# DC_Power_Regulation.net
KiCad netlist of a schematic drawn in Altium Designer
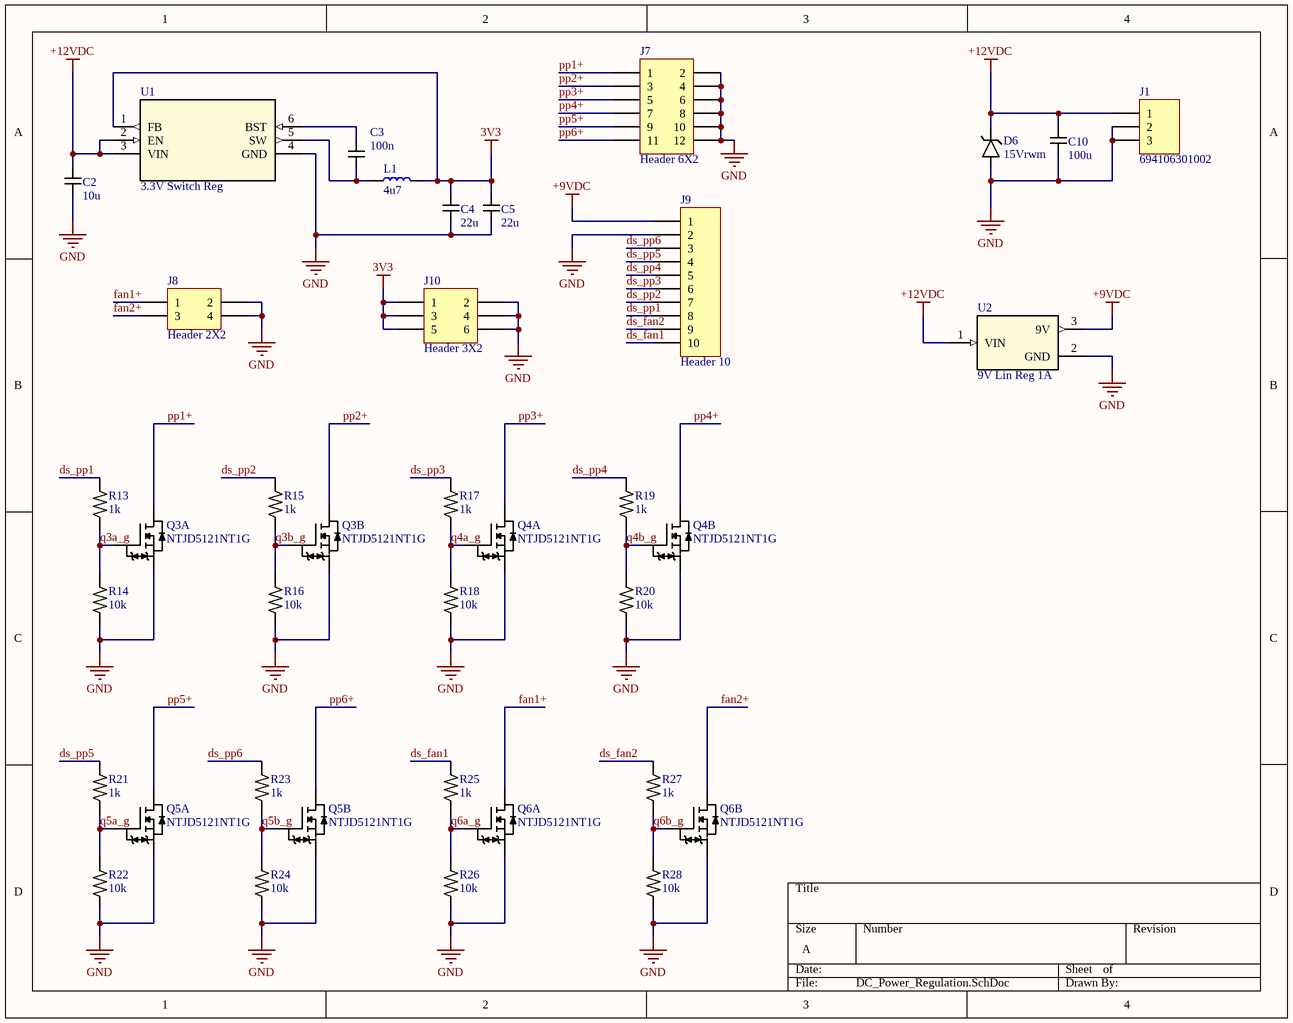
[diagram p0: DC_Power_Regulation.SchDoc]

(export (version "E")
  (design (tool "Eeschema 10.0.6"))
  (components
    (comp (ref "C2")
      (value "10u")
      (footprint "CAP_0805")
      (libsource (lib "PEAK_SCHEM_LIB") (part "CAP_0805"))
    )
    (comp (ref "C3")
      (value "100n")
      (footprint "CAP_0402")
      (libsource (lib "PEAK_SCHEM_LIB") (part "CAP_0402"))
    )
    (comp (ref "C4")
      (value "22u")
      (footprint "CAP_0805")
      (libsource (lib "PEAK_SCHEM_LIB") (part "CAP_0805"))
    )
    (comp (ref "C5")
      (value "22u")
      (footprint "CAP_0805")
      (libsource (lib "PEAK_SCHEM_LIB") (part "CAP_0805"))
    )
    (comp (ref "C10")
      (value "100u")
      (footprint "CAP_EEH-ZA1V151P_PAN")
      (libsource (lib "PEAK_SCHEM_LIB") (part "CAP_EEH-ZA1V151P_PAN"))
    )
    (comp (ref "D6")
      (value "15Vrwm")
      (footprint "SOD523")
      (description "ESD protection (TVS) diode in SOD523 package")
      (libsource (lib "PEAK_SCHEM_LIB") (part "PESD15VS1UB,115"))
    )
    (comp (ref "J1")
      (value "694106301002")
      (footprint "694106301002")
      (description "Header, 3-Pin")
      (fields (field (name "PUBLISHER") "Altium Limited"))
      (libsource (lib "Miscellaneous Connectors") (part "Header 3"))
    )
    (comp (ref "J7")
      (value "Header 6X2")
      (footprint "HDR2X6")
      (description "Header, 6-Pin, Dual row")
      (fields (field (name "PUBLISHER") "Altium Limited"))
      (libsource (lib "Miscellaneous Connectors") (part "Header 6X2"))
    )
    (comp (ref "J8")
      (value "Header 2X2")
      (footprint "HDR2X2")
      (description "Header, 2-Pin, Dual row")
      (fields (field (name "PUBLISHER") "Altium Limited"))
      (libsource (lib "Miscellaneous Connectors") (part "Header 2X2"))
    )
    (comp (ref "J9")
      (value "Header 10")
      (footprint "HDR1X10")
      (description "Header, 10-Pin")
      (fields (field (name "PUBLISHER") "Altium Limited"))
      (libsource (lib "Miscellaneous Connectors") (part "Header 10"))
    )
    (comp (ref "J10")
      (value "Header 3X2")
      (footprint "HDR2X3")
      (description "Header, 3-Pin, Dual row")
      (fields (field (name "PUBLISHER") "Altium Limited"))
      (libsource (lib "Miscellaneous Connectors") (part "Header 3X2"))
    )
    (comp (ref "L1")
      (value "4u7")
      (footprint "IND_0603")
      (description "Inductor SMD 0603")
      (libsource (lib "PEAK_SCHEM_LIB") (part "IND_0603"))
    )
    (comp (ref "Q3")
      (value "NTJD5121NT1G")
      (footprint "SOT-363")
      (description "2 NMOSFETs SOT-363")
      (libsource (lib "PEAK_SCHEM_LIB") (part "NTJD5121NT1G"))
    )
    (comp (ref "Q4")
      (value "NTJD5121NT1G")
      (footprint "SOT-363")
      (description "2 NMOSFETs SOT-363")
      (libsource (lib "PEAK_SCHEM_LIB") (part "NTJD5121NT1G"))
    )
    (comp (ref "Q5")
      (value "NTJD5121NT1G")
      (footprint "SOT-363")
      (description "2 NMOSFETs SOT-363")
      (libsource (lib "PEAK_SCHEM_LIB") (part "NTJD5121NT1G"))
    )
    (comp (ref "Q6")
      (value "NTJD5121NT1G")
      (footprint "SOT-363")
      (description "2 NMOSFETs SOT-363")
      (libsource (lib "PEAK_SCHEM_LIB") (part "NTJD5121NT1G"))
    )
    (comp (ref "R13")
      (value "1k")
      (footprint "RES_0402")
      (description "Resistor SMD 0402 (0.0625W)")
      (libsource (lib "PEAK_SCHEM_LIB") (part "RES_0402"))
    )
    (comp (ref "R14")
      (value "10k")
      (footprint "RES_0402")
      (description "Resistor SMD 0402 (0.0625W)")
      (libsource (lib "PEAK_SCHEM_LIB") (part "RES_0402"))
    )
    (comp (ref "R15")
      (value "1k")
      (footprint "RES_0402")
      (description "Resistor SMD 0402 (0.0625W)")
      (libsource (lib "PEAK_SCHEM_LIB") (part "RES_0402"))
    )
    (comp (ref "R16")
      (value "10k")
      (footprint "RES_0402")
      (description "Resistor SMD 0402 (0.0625W)")
      (libsource (lib "PEAK_SCHEM_LIB") (part "RES_0402"))
    )
    (comp (ref "R17")
      (value "1k")
      (footprint "RES_0402")
      (description "Resistor SMD 0402 (0.0625W)")
      (libsource (lib "PEAK_SCHEM_LIB") (part "RES_0402"))
    )
    (comp (ref "R18")
      (value "10k")
      (footprint "RES_0402")
      (description "Resistor SMD 0402 (0.0625W)")
      (libsource (lib "PEAK_SCHEM_LIB") (part "RES_0402"))
    )
    (comp (ref "R19")
      (value "1k")
      (footprint "RES_0402")
      (description "Resistor SMD 0402 (0.0625W)")
      (libsource (lib "PEAK_SCHEM_LIB") (part "RES_0402"))
    )
    (comp (ref "R20")
      (value "10k")
      (footprint "RES_0402")
      (description "Resistor SMD 0402 (0.0625W)")
      (libsource (lib "PEAK_SCHEM_LIB") (part "RES_0402"))
    )
    (comp (ref "R21")
      (value "1k")
      (footprint "RES_0402")
      (description "Resistor SMD 0402 (0.0625W)")
      (libsource (lib "PEAK_SCHEM_LIB") (part "RES_0402"))
    )
    (comp (ref "R22")
      (value "10k")
      (footprint "RES_0402")
      (description "Resistor SMD 0402 (0.0625W)")
      (libsource (lib "PEAK_SCHEM_LIB") (part "RES_0402"))
    )
    (comp (ref "R23")
      (value "1k")
      (footprint "RES_0402")
      (description "Resistor SMD 0402 (0.0625W)")
      (libsource (lib "PEAK_SCHEM_LIB") (part "RES_0402"))
    )
    (comp (ref "R24")
      (value "10k")
      (footprint "RES_0402")
      (description "Resistor SMD 0402 (0.0625W)")
      (libsource (lib "PEAK_SCHEM_LIB") (part "RES_0402"))
    )
    (comp (ref "R25")
      (value "1k")
      (footprint "RES_0402")
      (description "Resistor SMD 0402 (0.0625W)")
      (libsource (lib "PEAK_SCHEM_LIB") (part "RES_0402"))
    )
    (comp (ref "R26")
      (value "10k")
      (footprint "RES_0402")
      (description "Resistor SMD 0402 (0.0625W)")
      (libsource (lib "PEAK_SCHEM_LIB") (part "RES_0402"))
    )
    (comp (ref "R27")
      (value "1k")
      (footprint "RES_0402")
      (description "Resistor SMD 0402 (0.0625W)")
      (libsource (lib "PEAK_SCHEM_LIB") (part "RES_0402"))
    )
    (comp (ref "R28")
      (value "10k")
      (footprint "RES_0402")
      (description "Resistor SMD 0402 (0.0625W)")
      (libsource (lib "PEAK_SCHEM_LIB") (part "RES_0402"))
    )
    (comp (ref "U1")
      (value "3.3V Switch Reg")
      (footprint "AP63203WU-7")
      (description "IC REG BUCK 3.3V 2A TSOT23-6")
      (libsource (lib "PEAK_SCHEM_LIB") (part "AP63203WU-7"))
    )
    (comp (ref "U2")
      (value "9V Lin Reg 1A")
      (footprint "MC7809CTG")
      (description "IC REG LINEAR 9V 1A TO220AB")
      (libsource (lib "PEAK_SCHEM_LIB") (part "MC7809CTG"))
    )
  )
  (nets
    (net (code "1") (name "+9VDC") (class "Default")
      (node (ref "J9") (pin "1") (pinfunction "1_1") (pintype "passive"))
      (node (ref "U2") (pin "3") (pinfunction "9V_3") (pintype "output"))
    )
    (net (code "2") (name "+12VDC") (class "Default")
      (node (ref "C10") (pin "2") (pinfunction "2_2") (pintype "passive"))
      (node (ref "C2") (pin "2") (pinfunction "2_2") (pintype "passive"))
      (node (ref "D6") (pin "1") (pinfunction "V++_1") (pintype "passive"))
      (node (ref "J1") (pin "1") (pinfunction "1_1") (pintype "passive"))
      (node (ref "U1") (pin "2") (pinfunction "EN_2") (pintype "input"))
      (node (ref "U1") (pin "3") (pinfunction "VIN_3") (pintype "power_in"))
      (node (ref "U2") (pin "1") (pinfunction "VIN_1") (pintype "input"))
    )
    (net (code "3") (name "/ds_fan1") (class "Default")
      (node (ref "J9") (pin "10") (pinfunction "10_10") (pintype "passive"))
      (node (ref "R25") (pin "1") (pinfunction "1_1") (pintype "passive"))
    )
    (net (code "4") (name "/ds_fan2") (class "Default")
      (node (ref "J9") (pin "9") (pinfunction "9_9") (pintype "passive"))
      (node (ref "R27") (pin "1") (pinfunction "1_1") (pintype "passive"))
    )
    (net (code "5") (name "/ds_pp1") (class "Default")
      (node (ref "J9") (pin "8") (pinfunction "8_8") (pintype "passive"))
      (node (ref "R13") (pin "1") (pinfunction "1_1") (pintype "passive"))
    )
    (net (code "6") (name "/ds_pp2") (class "Default")
      (node (ref "J9") (pin "7") (pinfunction "7_7") (pintype "passive"))
      (node (ref "R15") (pin "1") (pinfunction "1_1") (pintype "passive"))
    )
    (net (code "7") (name "/ds_pp3") (class "Default")
      (node (ref "J9") (pin "6") (pinfunction "6_6") (pintype "passive"))
      (node (ref "R17") (pin "1") (pinfunction "1_1") (pintype "passive"))
    )
    (net (code "8") (name "/ds_pp4") (class "Default")
      (node (ref "J9") (pin "5") (pinfunction "5_5") (pintype "passive"))
      (node (ref "R19") (pin "1") (pinfunction "1_1") (pintype "passive"))
    )
    (net (code "9") (name "/ds_pp5") (class "Default")
      (node (ref "J9") (pin "4") (pinfunction "4_4") (pintype "passive"))
      (node (ref "R21") (pin "1") (pinfunction "1_1") (pintype "passive"))
    )
    (net (code "10") (name "/ds_pp6") (class "Default")
      (node (ref "J9") (pin "3") (pinfunction "3_3") (pintype "passive"))
      (node (ref "R23") (pin "1") (pinfunction "1_1") (pintype "passive"))
    )
    (net (code "11") (name "/fan1+") (class "Default")
      (node (ref "J8") (pin "1") (pinfunction "1_1") (pintype "passive"))
      (node (ref "Q6") (pin "1") (pinfunction "D1_1") (pintype "passive"))
    )
    (net (code "12") (name "/fan2+") (class "Default")
      (node (ref "J8") (pin "3") (pinfunction "3_3") (pintype "passive"))
      (node (ref "Q6") (pin "4") (pinfunction "D2_4") (pintype "passive"))
    )
    (net (code "13") (name "/pp1+") (class "Default")
      (node (ref "J7") (pin "1") (pinfunction "1_1") (pintype "passive"))
      (node (ref "Q3") (pin "1") (pinfunction "D1_1") (pintype "passive"))
    )
    (net (code "14") (name "/pp2+") (class "Default")
      (node (ref "J7") (pin "3") (pinfunction "3_3") (pintype "passive"))
      (node (ref "Q3") (pin "4") (pinfunction "D2_4") (pintype "passive"))
    )
    (net (code "15") (name "/pp3+") (class "Default")
      (node (ref "J7") (pin "5") (pinfunction "5_5") (pintype "passive"))
      (node (ref "Q4") (pin "1") (pinfunction "D1_1") (pintype "passive"))
    )
    (net (code "16") (name "/pp4+") (class "Default")
      (node (ref "J7") (pin "7") (pinfunction "7_7") (pintype "passive"))
      (node (ref "Q4") (pin "4") (pinfunction "D2_4") (pintype "passive"))
    )
    (net (code "17") (name "/pp5+") (class "Default")
      (node (ref "J7") (pin "9") (pinfunction "9_9") (pintype "passive"))
      (node (ref "Q5") (pin "1") (pinfunction "D1_1") (pintype "passive"))
    )
    (net (code "18") (name "/pp6+") (class "Default")
      (node (ref "J7") (pin "11") (pinfunction "11_11") (pintype "passive"))
      (node (ref "Q5") (pin "4") (pinfunction "D2_4") (pintype "passive"))
    )
    (net (code "19") (name "/q3a_g") (class "Default")
      (node (ref "Q3") (pin "2") (pinfunction "G1_2") (pintype "passive"))
      (node (ref "R13") (pin "2") (pinfunction "2_2") (pintype "passive"))
      (node (ref "R14") (pin "2") (pinfunction "2_2") (pintype "passive"))
    )
    (net (code "20") (name "/q3b_g") (class "Default")
      (node (ref "Q3") (pin "5") (pinfunction "G2_5") (pintype "passive"))
      (node (ref "R15") (pin "2") (pinfunction "2_2") (pintype "passive"))
      (node (ref "R16") (pin "2") (pinfunction "2_2") (pintype "passive"))
    )
    (net (code "21") (name "/q4a_g") (class "Default")
      (node (ref "Q4") (pin "2") (pinfunction "G1_2") (pintype "passive"))
      (node (ref "R17") (pin "2") (pinfunction "2_2") (pintype "passive"))
      (node (ref "R18") (pin "2") (pinfunction "2_2") (pintype "passive"))
    )
    (net (code "22") (name "/q4b_g") (class "Default")
      (node (ref "Q4") (pin "5") (pinfunction "G2_5") (pintype "passive"))
      (node (ref "R19") (pin "2") (pinfunction "2_2") (pintype "passive"))
      (node (ref "R20") (pin "2") (pinfunction "2_2") (pintype "passive"))
    )
    (net (code "23") (name "/q5a_g") (class "Default")
      (node (ref "Q5") (pin "2") (pinfunction "G1_2") (pintype "passive"))
      (node (ref "R21") (pin "2") (pinfunction "2_2") (pintype "passive"))
      (node (ref "R22") (pin "2") (pinfunction "2_2") (pintype "passive"))
    )
    (net (code "24") (name "/q5b_g") (class "Default")
      (node (ref "Q5") (pin "5") (pinfunction "G2_5") (pintype "passive"))
      (node (ref "R23") (pin "2") (pinfunction "2_2") (pintype "passive"))
      (node (ref "R24") (pin "2") (pinfunction "2_2") (pintype "passive"))
    )
    (net (code "25") (name "/q6a_g") (class "Default")
      (node (ref "Q6") (pin "2") (pinfunction "G1_2") (pintype "passive"))
      (node (ref "R25") (pin "2") (pinfunction "2_2") (pintype "passive"))
      (node (ref "R26") (pin "2") (pinfunction "2_2") (pintype "passive"))
    )
    (net (code "26") (name "/q6b_g") (class "Default")
      (node (ref "Q6") (pin "5") (pinfunction "G2_5") (pintype "passive"))
      (node (ref "R27") (pin "2") (pinfunction "2_2") (pintype "passive"))
      (node (ref "R28") (pin "2") (pinfunction "2_2") (pintype "passive"))
    )
    (net (code "27") (name "3V3") (class "Default")
      (node (ref "C4") (pin "2") (pinfunction "2_2") (pintype "passive"))
      (node (ref "C5") (pin "2") (pinfunction "2_2") (pintype "passive"))
      (node (ref "J10") (pin "1") (pinfunction "1_1") (pintype "passive"))
      (node (ref "J10") (pin "3") (pinfunction "3_3") (pintype "passive"))
      (node (ref "J10") (pin "5") (pinfunction "5_5") (pintype "passive"))
      (node (ref "L1") (pin "2") (pinfunction "2_2") (pintype "passive"))
      (node (ref "U1") (pin "1") (pinfunction "FB_1") (pintype "output"))
    )
    (net (code "28") (name "GND") (class "Default")
      (node (ref "C10") (pin "1") (pinfunction "1_1") (pintype "passive"))
      (node (ref "C2") (pin "1") (pinfunction "1_1") (pintype "passive"))
      (node (ref "C4") (pin "1") (pinfunction "1_1") (pintype "passive"))
      (node (ref "C5") (pin "1") (pinfunction "1_1") (pintype "passive"))
      (node (ref "D6") (pin "2") (pinfunction "GND_2") (pintype "passive"))
      (node (ref "J1") (pin "2") (pinfunction "2_2") (pintype "passive"))
      (node (ref "J1") (pin "3") (pinfunction "3_3") (pintype "passive"))
      (node (ref "J10") (pin "2") (pinfunction "2_2") (pintype "passive"))
      (node (ref "J10") (pin "4") (pinfunction "4_4") (pintype "passive"))
      (node (ref "J10") (pin "6") (pinfunction "6_6") (pintype "passive"))
      (node (ref "J7") (pin "10") (pinfunction "10_10") (pintype "passive"))
      (node (ref "J7") (pin "12") (pinfunction "12_12") (pintype "passive"))
      (node (ref "J7") (pin "2") (pinfunction "2_2") (pintype "passive"))
      (node (ref "J7") (pin "4") (pinfunction "4_4") (pintype "passive"))
      (node (ref "J7") (pin "6") (pinfunction "6_6") (pintype "passive"))
      (node (ref "J7") (pin "8") (pinfunction "8_8") (pintype "passive"))
      (node (ref "J8") (pin "2") (pinfunction "2_2") (pintype "passive"))
      (node (ref "J8") (pin "4") (pinfunction "4_4") (pintype "passive"))
      (node (ref "J9") (pin "2") (pinfunction "2_2") (pintype "passive"))
      (node (ref "Q3") (pin "3") (pinfunction "S1_3") (pintype "passive"))
      (node (ref "Q3") (pin "6") (pinfunction "S2_6") (pintype "passive"))
      (node (ref "Q4") (pin "3") (pinfunction "S1_3") (pintype "passive"))
      (node (ref "Q4") (pin "6") (pinfunction "S2_6") (pintype "passive"))
      (node (ref "Q5") (pin "3") (pinfunction "S1_3") (pintype "passive"))
      (node (ref "Q5") (pin "6") (pinfunction "S2_6") (pintype "passive"))
      (node (ref "Q6") (pin "3") (pinfunction "S1_3") (pintype "passive"))
      (node (ref "Q6") (pin "6") (pinfunction "S2_6") (pintype "passive"))
      (node (ref "R14") (pin "1") (pinfunction "1_1") (pintype "passive"))
      (node (ref "R16") (pin "1") (pinfunction "1_1") (pintype "passive"))
      (node (ref "R18") (pin "1") (pinfunction "1_1") (pintype "passive"))
      (node (ref "R20") (pin "1") (pinfunction "1_1") (pintype "passive"))
      (node (ref "R22") (pin "1") (pinfunction "1_1") (pintype "passive"))
      (node (ref "R24") (pin "1") (pinfunction "1_1") (pintype "passive"))
      (node (ref "R26") (pin "1") (pinfunction "1_1") (pintype "passive"))
      (node (ref "R28") (pin "1") (pinfunction "1_1") (pintype "passive"))
      (node (ref "U1") (pin "4") (pinfunction "GND_4") (pintype "power_in"))
      (node (ref "U2") (pin "2") (pinfunction "GND_2") (pintype "power_in"))
    )
    (net (code "29") (name "Net-(U1-BST)") (class "Default")
      (node (ref "C3") (pin "2") (pinfunction "2_2") (pintype "passive"))
      (node (ref "U1") (pin "6") (pinfunction "BST_6") (pintype "input"))
    )
    (net (code "30") (name "Net-(U1-SW)") (class "Default")
      (node (ref "C3") (pin "1") (pinfunction "1_1") (pintype "passive"))
      (node (ref "L1") (pin "1") (pinfunction "1_1") (pintype "passive"))
      (node (ref "U1") (pin "5") (pinfunction "SW_5") (pintype "output"))
    )
  )
)
